# TSC8-75pld.net
KiCad netlist of a schematic drawn in EAGLE
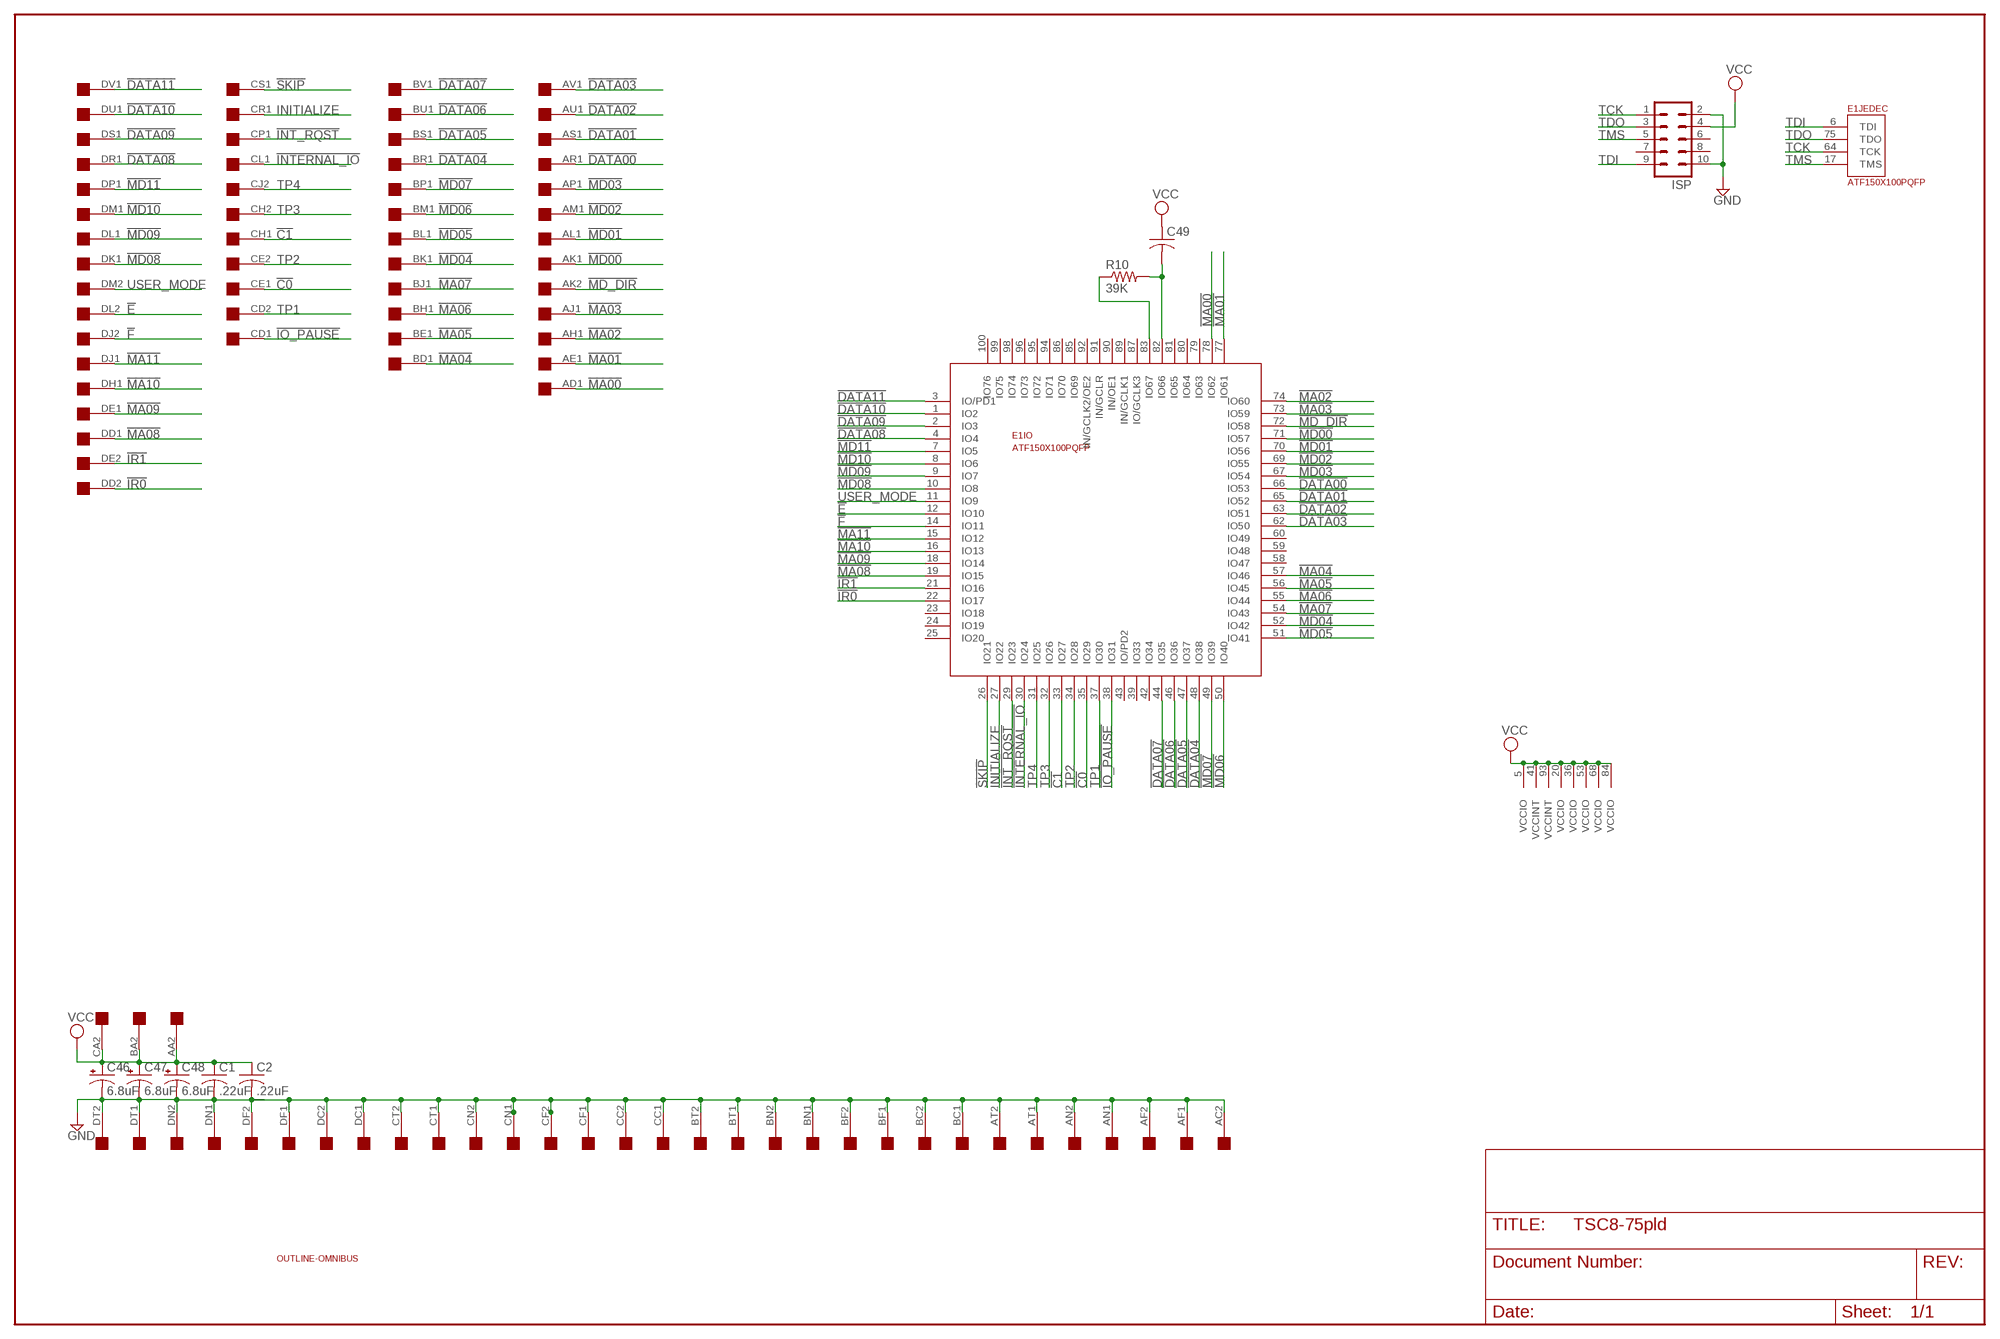
[diagram p0: schematic, sheet 1]

(export (version "E")
  (design (tool "Eeschema 10.0.6"))
  (components
    (comp (ref "C1")
      (value ".22uF")
      (footprint "eagle-import:C050-025X075")
      (libsource (lib "eagle-import") (part "C-US050-025X075"))
    )
    (comp (ref "C2")
      (value ".22uF")
      (footprint "eagle-import:C050-025X075")
      (libsource (lib "eagle-import") (part "C-US050-025X075"))
    )
    (comp (ref "C46")
      (value "6.8uF")
      (footprint "eagle-import:E12-8")
      (libsource (lib "eagle-import") (part "CPOL-USE20-8AXIAL"))
    )
    (comp (ref "C47")
      (value "6.8uF")
      (footprint "eagle-import:E12-8")
      (libsource (lib "eagle-import") (part "CPOL-USE20-8AXIAL"))
    )
    (comp (ref "C48")
      (value "6.8uF")
      (footprint "eagle-import:E12-8")
      (libsource (lib "eagle-import") (part "CPOL-USE20-8AXIAL"))
    )
    (comp (ref "C49")
      (value "C-US050-025X075")
      (footprint "eagle-import:C050-025X075")
      (libsource (lib "eagle-import") (part "C-US050-025X075"))
    )
    (comp (ref "E1")
      (value "ATF150X100PQFP")
      (footprint "eagle-import:PQFP-100")
      (libsource (lib "eagle-import") (part "ATF150X100PQFP"))
    )
    (comp (ref "EDGE")
      (value "QUAD")
      (footprint "eagle-import:EDGE-CON8")
      (libsource (lib "eagle-import") (part "QUAD"))
    )
    (comp (ref "ISP")
      (value "ML10")
      (footprint "eagle-import:ML10")
      (libsource (lib "eagle-import") (part "ML10"))
    )
    (comp (ref "R10")
      (value "39K")
      (footprint "eagle-import:0204_7")
      (libsource (lib "eagle-import") (part "R-US_0204/7"))
    )
    (comp (ref "U$1")
      (value "OUTLINE-OMNIBUS")
      (footprint "eagle-import:OMNIBUS")
      (libsource (lib "eagle-import") (part "OUTLINE-OMNIBUS"))
    )
  )
  (nets
    (net (code "1") (name "/INITIALIZE") (class "Default")
      (node (ref "E1") (pin "27") (pinfunction "IO22_27") (pintype "bidirectional"))
      (node (ref "EDGE") (pin "CR1") (pinfunction "1_CR1") (pintype "bidirectional"))
    )
    (net (code "2") (name "/TCK") (class "Default")
      (node (ref "E1") (pin "64") (pinfunction "TCK_64") (pintype "bidirectional"))
      (node (ref "ISP") (pin "1") (pinfunction "1_1") (pintype "passive"))
    )
    (net (code "3") (name "/TDI") (class "Default")
      (node (ref "E1") (pin "6") (pinfunction "TDI_6") (pintype "bidirectional"))
      (node (ref "ISP") (pin "9") (pinfunction "9_9") (pintype "passive"))
    )
    (net (code "4") (name "/TDO") (class "Default")
      (node (ref "E1") (pin "75") (pinfunction "TDO_75") (pintype "bidirectional"))
      (node (ref "ISP") (pin "3") (pinfunction "3_3") (pintype "passive"))
    )
    (net (code "5") (name "/TMS") (class "Default")
      (node (ref "E1") (pin "17") (pinfunction "TMS_17") (pintype "bidirectional"))
      (node (ref "ISP") (pin "5") (pinfunction "5_5") (pintype "passive"))
    )
    (net (code "6") (name "/TP1") (class "Default")
      (node (ref "E1") (pin "37") (pinfunction "IO30_37") (pintype "bidirectional"))
      (node (ref "EDGE") (pin "CD2") (pinfunction "1_CD2") (pintype "bidirectional"))
    )
    (net (code "7") (name "/TP2") (class "Default")
      (node (ref "E1") (pin "34") (pinfunction "IO28_34") (pintype "bidirectional"))
      (node (ref "EDGE") (pin "CE2") (pinfunction "1_CE2") (pintype "bidirectional"))
    )
    (net (code "8") (name "/TP3") (class "Default")
      (node (ref "E1") (pin "32") (pinfunction "IO26_32") (pintype "bidirectional"))
      (node (ref "EDGE") (pin "CH2") (pinfunction "1_CH2") (pintype "bidirectional"))
    )
    (net (code "9") (name "/TP4") (class "Default")
      (node (ref "E1") (pin "31") (pinfunction "IO25_31") (pintype "bidirectional"))
      (node (ref "EDGE") (pin "CJ2") (pinfunction "1_CJ2") (pintype "bidirectional"))
    )
    (net (code "10") (name "/USER_MODE") (class "Default")
      (node (ref "E1") (pin "11") (pinfunction "IO9_11") (pintype "bidirectional"))
      (node (ref "EDGE") (pin "DM2") (pinfunction "1_DM2") (pintype "bidirectional"))
    )
    (net (code "11") (name "/~{C0}") (class "Default")
      (node (ref "E1") (pin "35") (pinfunction "IO29_35") (pintype "bidirectional"))
      (node (ref "EDGE") (pin "CE1") (pinfunction "1_CE1") (pintype "bidirectional"))
    )
    (net (code "12") (name "/~{C1}") (class "Default")
      (node (ref "E1") (pin "33") (pinfunction "IO27_33") (pintype "bidirectional"))
      (node (ref "EDGE") (pin "CH1") (pinfunction "1_CH1") (pintype "bidirectional"))
    )
    (net (code "13") (name "/~{DATA00}") (class "Default")
      (node (ref "E1") (pin "66") (pinfunction "IO53_66") (pintype "bidirectional"))
      (node (ref "EDGE") (pin "AR1") (pinfunction "1_AR1") (pintype "bidirectional"))
    )
    (net (code "14") (name "/~{DATA01}") (class "Default")
      (node (ref "E1") (pin "65") (pinfunction "IO52_65") (pintype "bidirectional"))
      (node (ref "EDGE") (pin "AS1") (pinfunction "1_AS1") (pintype "bidirectional"))
    )
    (net (code "15") (name "/~{DATA02}") (class "Default")
      (node (ref "E1") (pin "63") (pinfunction "IO51_63") (pintype "bidirectional"))
      (node (ref "EDGE") (pin "AU1") (pinfunction "1_AU1") (pintype "bidirectional"))
    )
    (net (code "16") (name "/~{DATA03}") (class "Default")
      (node (ref "E1") (pin "62") (pinfunction "IO50_62") (pintype "bidirectional"))
      (node (ref "EDGE") (pin "AV1") (pinfunction "1_AV1") (pintype "bidirectional"))
    )
    (net (code "17") (name "/~{DATA04}") (class "Default")
      (node (ref "E1") (pin "48") (pinfunction "IO38_48") (pintype "bidirectional"))
      (node (ref "EDGE") (pin "BR1") (pinfunction "1_BR1") (pintype "bidirectional"))
    )
    (net (code "18") (name "/~{DATA05}") (class "Default")
      (node (ref "E1") (pin "47") (pinfunction "IO37_47") (pintype "bidirectional"))
      (node (ref "EDGE") (pin "BS1") (pinfunction "1_BS1") (pintype "bidirectional"))
    )
    (net (code "19") (name "/~{DATA06}") (class "Default")
      (node (ref "E1") (pin "46") (pinfunction "IO36_46") (pintype "bidirectional"))
      (node (ref "EDGE") (pin "BU1") (pinfunction "1_BU1") (pintype "bidirectional"))
    )
    (net (code "20") (name "/~{DATA07}") (class "Default")
      (node (ref "E1") (pin "44") (pinfunction "IO35_44") (pintype "bidirectional"))
      (node (ref "EDGE") (pin "BV1") (pinfunction "1_BV1") (pintype "bidirectional"))
    )
    (net (code "21") (name "/~{DATA08}") (class "Default")
      (node (ref "E1") (pin "4") (pinfunction "IO4_4") (pintype "bidirectional"))
      (node (ref "EDGE") (pin "DR1") (pinfunction "1_DR1") (pintype "bidirectional"))
    )
    (net (code "22") (name "/~{DATA09}") (class "Default")
      (node (ref "E1") (pin "2") (pinfunction "IO3_2") (pintype "bidirectional"))
      (node (ref "EDGE") (pin "DS1") (pinfunction "1_DS1") (pintype "bidirectional"))
    )
    (net (code "23") (name "/~{DATA10}") (class "Default")
      (node (ref "E1") (pin "1") (pinfunction "IO2_1") (pintype "bidirectional"))
      (node (ref "EDGE") (pin "DU1") (pinfunction "1_DU1") (pintype "bidirectional"))
    )
    (net (code "24") (name "/~{DATA11}") (class "Default")
      (node (ref "E1") (pin "3") (pinfunction "IO/PD1_3") (pintype "bidirectional"))
      (node (ref "EDGE") (pin "DV1") (pinfunction "1_DV1") (pintype "bidirectional"))
    )
    (net (code "25") (name "/~{E}") (class "Default")
      (node (ref "E1") (pin "12") (pinfunction "IO10_12") (pintype "bidirectional"))
      (node (ref "EDGE") (pin "DL2") (pinfunction "1_DL2") (pintype "bidirectional"))
    )
    (net (code "26") (name "/~{F}") (class "Default")
      (node (ref "E1") (pin "14") (pinfunction "IO11_14") (pintype "bidirectional"))
      (node (ref "EDGE") (pin "DJ2") (pinfunction "1_DJ2") (pintype "bidirectional"))
    )
    (net (code "27") (name "/~{INTERNAL_IO}") (class "Default")
      (node (ref "E1") (pin "30") (pinfunction "IO24_30") (pintype "bidirectional"))
      (node (ref "EDGE") (pin "CL1") (pinfunction "1_CL1") (pintype "bidirectional"))
    )
    (net (code "28") (name "/~{INT_RQST}") (class "Default")
      (node (ref "E1") (pin "29") (pinfunction "IO23_29") (pintype "bidirectional"))
      (node (ref "EDGE") (pin "CP1") (pinfunction "1_CP1") (pintype "bidirectional"))
    )
    (net (code "29") (name "/~{IO_PAUSE}") (class "Default")
      (node (ref "E1") (pin "38") (pinfunction "IO31_38") (pintype "bidirectional"))
      (node (ref "EDGE") (pin "CD1") (pinfunction "1_CD1") (pintype "bidirectional"))
    )
    (net (code "30") (name "/~{IR0}") (class "Default")
      (node (ref "E1") (pin "22") (pinfunction "IO17_22") (pintype "bidirectional"))
      (node (ref "EDGE") (pin "DD2") (pinfunction "1_DD2") (pintype "bidirectional"))
    )
    (net (code "31") (name "/~{IR1}") (class "Default")
      (node (ref "E1") (pin "21") (pinfunction "IO16_21") (pintype "bidirectional"))
      (node (ref "EDGE") (pin "DE2") (pinfunction "1_DE2") (pintype "bidirectional"))
    )
    (net (code "32") (name "/~{MA00}") (class "Default")
      (node (ref "E1") (pin "78") (pinfunction "IO62_78") (pintype "bidirectional"))
      (node (ref "EDGE") (pin "AD1") (pinfunction "1_AD1") (pintype "bidirectional"))
    )
    (net (code "33") (name "/~{MA01}") (class "Default")
      (node (ref "E1") (pin "77") (pinfunction "IO61_77") (pintype "bidirectional"))
      (node (ref "EDGE") (pin "AE1") (pinfunction "1_AE1") (pintype "bidirectional"))
    )
    (net (code "34") (name "/~{MA02}") (class "Default")
      (node (ref "E1") (pin "74") (pinfunction "IO60_74") (pintype "bidirectional"))
      (node (ref "EDGE") (pin "AH1") (pinfunction "1_AH1") (pintype "bidirectional"))
    )
    (net (code "35") (name "/~{MA03}") (class "Default")
      (node (ref "E1") (pin "73") (pinfunction "IO59_73") (pintype "bidirectional"))
      (node (ref "EDGE") (pin "AJ1") (pinfunction "1_AJ1") (pintype "bidirectional"))
    )
    (net (code "36") (name "/~{MA04}") (class "Default")
      (node (ref "E1") (pin "57") (pinfunction "IO46_57") (pintype "bidirectional"))
      (node (ref "EDGE") (pin "BD1") (pinfunction "1_BD1") (pintype "bidirectional"))
    )
    (net (code "37") (name "/~{MA05}") (class "Default")
      (node (ref "E1") (pin "56") (pinfunction "IO45_56") (pintype "bidirectional"))
      (node (ref "EDGE") (pin "BE1") (pinfunction "1_BE1") (pintype "bidirectional"))
    )
    (net (code "38") (name "/~{MA06}") (class "Default")
      (node (ref "E1") (pin "55") (pinfunction "IO44_55") (pintype "bidirectional"))
      (node (ref "EDGE") (pin "BH1") (pinfunction "1_BH1") (pintype "bidirectional"))
    )
    (net (code "39") (name "/~{MA07}") (class "Default")
      (node (ref "E1") (pin "54") (pinfunction "IO43_54") (pintype "bidirectional"))
      (node (ref "EDGE") (pin "BJ1") (pinfunction "1_BJ1") (pintype "bidirectional"))
    )
    (net (code "40") (name "/~{MA08}") (class "Default")
      (node (ref "E1") (pin "19") (pinfunction "IO15_19") (pintype "bidirectional"))
      (node (ref "EDGE") (pin "DD1") (pinfunction "1_DD1") (pintype "bidirectional"))
    )
    (net (code "41") (name "/~{MA09}") (class "Default")
      (node (ref "E1") (pin "18") (pinfunction "IO14_18") (pintype "bidirectional"))
      (node (ref "EDGE") (pin "DE1") (pinfunction "1_DE1") (pintype "bidirectional"))
    )
    (net (code "42") (name "/~{MA10}") (class "Default")
      (node (ref "E1") (pin "16") (pinfunction "IO13_16") (pintype "bidirectional"))
      (node (ref "EDGE") (pin "DH1") (pinfunction "1_DH1") (pintype "bidirectional"))
    )
    (net (code "43") (name "/~{MA11}") (class "Default")
      (node (ref "E1") (pin "15") (pinfunction "IO12_15") (pintype "bidirectional"))
      (node (ref "EDGE") (pin "DJ1") (pinfunction "1_DJ1") (pintype "bidirectional"))
    )
    (net (code "44") (name "/~{MD00}") (class "Default")
      (node (ref "E1") (pin "71") (pinfunction "IO57_71") (pintype "bidirectional"))
      (node (ref "EDGE") (pin "AK1") (pinfunction "1_AK1") (pintype "bidirectional"))
    )
    (net (code "45") (name "/~{MD01}") (class "Default")
      (node (ref "E1") (pin "70") (pinfunction "IO56_70") (pintype "bidirectional"))
      (node (ref "EDGE") (pin "AL1") (pinfunction "1_AL1") (pintype "bidirectional"))
    )
    (net (code "46") (name "/~{MD02}") (class "Default")
      (node (ref "E1") (pin "69") (pinfunction "IO55_69") (pintype "bidirectional"))
      (node (ref "EDGE") (pin "AM1") (pinfunction "1_AM1") (pintype "bidirectional"))
    )
    (net (code "47") (name "/~{MD03}") (class "Default")
      (node (ref "E1") (pin "67") (pinfunction "IO54_67") (pintype "bidirectional"))
      (node (ref "EDGE") (pin "AP1") (pinfunction "1_AP1") (pintype "bidirectional"))
    )
    (net (code "48") (name "/~{MD04}") (class "Default")
      (node (ref "E1") (pin "52") (pinfunction "IO42_52") (pintype "bidirectional"))
      (node (ref "EDGE") (pin "BK1") (pinfunction "1_BK1") (pintype "bidirectional"))
    )
    (net (code "49") (name "/~{MD05}") (class "Default")
      (node (ref "E1") (pin "51") (pinfunction "IO41_51") (pintype "bidirectional"))
      (node (ref "EDGE") (pin "BL1") (pinfunction "1_BL1") (pintype "bidirectional"))
    )
    (net (code "50") (name "/~{MD06}") (class "Default")
      (node (ref "E1") (pin "50") (pinfunction "IO40_50") (pintype "bidirectional"))
      (node (ref "EDGE") (pin "BM1") (pinfunction "1_BM1") (pintype "bidirectional"))
    )
    (net (code "51") (name "/~{MD07}") (class "Default")
      (node (ref "E1") (pin "49") (pinfunction "IO39_49") (pintype "bidirectional"))
      (node (ref "EDGE") (pin "BP1") (pinfunction "1_BP1") (pintype "bidirectional"))
    )
    (net (code "52") (name "/~{MD08}") (class "Default")
      (node (ref "E1") (pin "10") (pinfunction "IO8_10") (pintype "bidirectional"))
      (node (ref "EDGE") (pin "DK1") (pinfunction "1_DK1") (pintype "bidirectional"))
    )
    (net (code "53") (name "/~{MD09}") (class "Default")
      (node (ref "E1") (pin "9") (pinfunction "IO7_9") (pintype "bidirectional"))
      (node (ref "EDGE") (pin "DL1") (pinfunction "1_DL1") (pintype "bidirectional"))
    )
    (net (code "54") (name "/~{MD10}") (class "Default")
      (node (ref "E1") (pin "8") (pinfunction "IO6_8") (pintype "bidirectional"))
      (node (ref "EDGE") (pin "DM1") (pinfunction "1_DM1") (pintype "bidirectional"))
    )
    (net (code "55") (name "/~{MD11}") (class "Default")
      (node (ref "E1") (pin "7") (pinfunction "IO5_7") (pintype "bidirectional"))
      (node (ref "EDGE") (pin "DP1") (pinfunction "1_DP1") (pintype "bidirectional"))
    )
    (net (code "56") (name "/~{MD_DIR}") (class "Default")
      (node (ref "E1") (pin "72") (pinfunction "IO58_72") (pintype "bidirectional"))
      (node (ref "EDGE") (pin "AK2") (pinfunction "1_AK2") (pintype "bidirectional"))
    )
    (net (code "57") (name "/~{SKIP}") (class "Default")
      (node (ref "E1") (pin "26") (pinfunction "IO21_26") (pintype "bidirectional"))
      (node (ref "EDGE") (pin "CS1") (pinfunction "1_CS1") (pintype "bidirectional"))
    )
    (net (code "58") (name "GND") (class "Default")
      (node (ref "C1") (pin "2") (pinfunction "2_2") (pintype "passive"))
      (node (ref "C2") (pin "2") (pinfunction "2_2") (pintype "passive"))
      (node (ref "C46") (pin "-") (pinfunction "-_-") (pintype "passive"))
      (node (ref "C47") (pin "-") (pinfunction "-_-") (pintype "passive"))
      (node (ref "C48") (pin "-") (pinfunction "-_-") (pintype "passive"))
      (node (ref "EDGE") (pin "AC2") (pinfunction "1_AC2") (pintype "bidirectional"))
      (node (ref "EDGE") (pin "AF1") (pinfunction "1_AF1") (pintype "bidirectional"))
      (node (ref "EDGE") (pin "AF2") (pinfunction "1_AF2") (pintype "bidirectional"))
      (node (ref "EDGE") (pin "AN1") (pinfunction "1_AN1") (pintype "bidirectional"))
      (node (ref "EDGE") (pin "AN2") (pinfunction "1_AN2") (pintype "bidirectional"))
      (node (ref "EDGE") (pin "AT1") (pinfunction "1_AT1") (pintype "bidirectional"))
      (node (ref "EDGE") (pin "AT2") (pinfunction "1_AT2") (pintype "bidirectional"))
      (node (ref "EDGE") (pin "BC1") (pinfunction "1_BC1") (pintype "bidirectional"))
      (node (ref "EDGE") (pin "BC2") (pinfunction "1_BC2") (pintype "bidirectional"))
      (node (ref "EDGE") (pin "BF1") (pinfunction "1_BF1") (pintype "bidirectional"))
      (node (ref "EDGE") (pin "BF2") (pinfunction "1_BF2") (pintype "bidirectional"))
      (node (ref "EDGE") (pin "BN1") (pinfunction "1_BN1") (pintype "bidirectional"))
      (node (ref "EDGE") (pin "BN2") (pinfunction "1_BN2") (pintype "bidirectional"))
      (node (ref "EDGE") (pin "BT1") (pinfunction "1_BT1") (pintype "bidirectional"))
      (node (ref "EDGE") (pin "BT2") (pinfunction "1_BT2") (pintype "bidirectional"))
      (node (ref "EDGE") (pin "CC1") (pinfunction "1_CC1") (pintype "bidirectional"))
      (node (ref "EDGE") (pin "CC2") (pinfunction "1_CC2") (pintype "bidirectional"))
      (node (ref "EDGE") (pin "CF1") (pinfunction "1_CF1") (pintype "bidirectional"))
      (node (ref "EDGE") (pin "CF2") (pinfunction "1_CF2") (pintype "bidirectional"))
      (node (ref "EDGE") (pin "CN1") (pinfunction "1_CN1") (pintype "bidirectional"))
      (node (ref "EDGE") (pin "CN2") (pinfunction "1_CN2") (pintype "bidirectional"))
      (node (ref "EDGE") (pin "CT1") (pinfunction "1_CT1") (pintype "bidirectional"))
      (node (ref "EDGE") (pin "CT2") (pinfunction "1_CT2") (pintype "bidirectional"))
      (node (ref "EDGE") (pin "DC1") (pinfunction "1_DC1") (pintype "bidirectional"))
      (node (ref "EDGE") (pin "DC2") (pinfunction "1_DC2") (pintype "bidirectional"))
      (node (ref "EDGE") (pin "DF1") (pinfunction "1_DF1") (pintype "bidirectional"))
      (node (ref "EDGE") (pin "DF2") (pinfunction "1_DF2") (pintype "bidirectional"))
      (node (ref "EDGE") (pin "DN1") (pinfunction "1_DN1") (pintype "bidirectional"))
      (node (ref "EDGE") (pin "DN2") (pinfunction "1_DN2") (pintype "bidirectional"))
      (node (ref "EDGE") (pin "DT1") (pinfunction "1_DT1") (pintype "bidirectional"))
      (node (ref "EDGE") (pin "DT2") (pinfunction "1_DT2") (pintype "bidirectional"))
      (node (ref "ISP") (pin "10") (pinfunction "10_10") (pintype "passive"))
      (node (ref "ISP") (pin "2") (pinfunction "2_2") (pintype "passive"))
    )
    (net (code "59") (name "Net-(E1Q-IO66)") (class "Default")
      (node (ref "C49") (pin "2") (pinfunction "2_2") (pintype "passive"))
      (node (ref "E1") (pin "82") (pinfunction "IO66_82") (pintype "bidirectional"))
      (node (ref "R10") (pin "2") (pinfunction "2_2") (pintype "passive"))
    )
    (net (code "60") (name "Net-(E1Q-IO67)") (class "Default")
      (node (ref "E1") (pin "83") (pinfunction "IO67_83") (pintype "bidirectional"))
      (node (ref "R10") (pin "1") (pinfunction "1_1") (pintype "passive"))
    )
    (net (code "61") (name "VCC") (class "Default")
      (node (ref "C1") (pin "1") (pinfunction "1_1") (pintype "passive"))
      (node (ref "C2") (pin "1") (pinfunction "1_1") (pintype "passive"))
      (node (ref "C46") (pin "+") (pinfunction "+_+") (pintype "passive"))
      (node (ref "C47") (pin "+") (pinfunction "+_+") (pintype "passive"))
      (node (ref "C48") (pin "+") (pinfunction "+_+") (pintype "passive"))
      (node (ref "C49") (pin "1") (pinfunction "1_1") (pintype "passive"))
      (node (ref "E1") (pin "20") (pinfunction "VCCIO_20") (pintype "power_in"))
      (node (ref "E1") (pin "36") (pinfunction "VCCIO_36") (pintype "power_in"))
      (node (ref "E1") (pin "41") (pinfunction "VCCINT_41") (pintype "power_in"))
      (node (ref "E1") (pin "5") (pinfunction "VCCIO_5") (pintype "power_in"))
      (node (ref "E1") (pin "53") (pinfunction "VCCIO_53") (pintype "power_in"))
      (node (ref "E1") (pin "68") (pinfunction "VCCIO_68") (pintype "power_in"))
      (node (ref "E1") (pin "84") (pinfunction "VCCIO_84") (pintype "power_in"))
      (node (ref "E1") (pin "93") (pinfunction "VCCINT_93") (pintype "power_in"))
      (node (ref "EDGE") (pin "AA2") (pinfunction "1_AA2") (pintype "bidirectional"))
      (node (ref "EDGE") (pin "BA2") (pinfunction "1_BA2") (pintype "bidirectional"))
      (node (ref "EDGE") (pin "CA2") (pinfunction "1_CA2") (pintype "bidirectional"))
      (node (ref "ISP") (pin "4") (pinfunction "4_4") (pintype "passive"))
    )
    (net (code "62") (name "unconnected-(E1Q-IN{slash}GCLK1-Pad89)") (class "Default")
      (node (ref "E1") (pin "89") (pinfunction "IN/GCLK1_89") (pintype "input"))
    )
    (net (code "63") (name "unconnected-(E1Q-IN{slash}GCLK2{slash}OE2-Pad92)") (class "Default")
      (node (ref "E1") (pin "92") (pinfunction "IN/GCLK2/OE2_92") (pintype "input"))
    )
    (net (code "64") (name "unconnected-(E1Q-IN{slash}GCLR-Pad91)") (class "Default")
      (node (ref "E1") (pin "91") (pinfunction "IN/GCLR_91") (pintype "input"))
    )
    (net (code "65") (name "unconnected-(E1Q-IN{slash}OE1-Pad90)") (class "Default")
      (node (ref "E1") (pin "90") (pinfunction "IN/OE1_90") (pintype "input"))
    )
    (net (code "66") (name "unconnected-(E1Q-IO18-Pad23)") (class "Default")
      (node (ref "E1") (pin "23") (pinfunction "IO18_23") (pintype "bidirectional"))
    )
    (net (code "67") (name "unconnected-(E1Q-IO19-Pad24)") (class "Default")
      (node (ref "E1") (pin "24") (pinfunction "IO19_24") (pintype "bidirectional"))
    )
    (net (code "68") (name "unconnected-(E1Q-IO20-Pad25)") (class "Default")
      (node (ref "E1") (pin "25") (pinfunction "IO20_25") (pintype "bidirectional"))
    )
    (net (code "69") (name "unconnected-(E1Q-IO33-Pad39)") (class "Default")
      (node (ref "E1") (pin "39") (pinfunction "IO33_39") (pintype "bidirectional"))
    )
    (net (code "70") (name "unconnected-(E1Q-IO34-Pad42)") (class "Default")
      (node (ref "E1") (pin "42") (pinfunction "IO34_42") (pintype "bidirectional"))
    )
    (net (code "71") (name "unconnected-(E1Q-IO47-Pad58)") (class "Default")
      (node (ref "E1") (pin "58") (pinfunction "IO47_58") (pintype "bidirectional"))
    )
    (net (code "72") (name "unconnected-(E1Q-IO48-Pad59)") (class "Default")
      (node (ref "E1") (pin "59") (pinfunction "IO48_59") (pintype "bidirectional"))
    )
    (net (code "73") (name "unconnected-(E1Q-IO49-Pad60)") (class "Default")
      (node (ref "E1") (pin "60") (pinfunction "IO49_60") (pintype "bidirectional"))
    )
    (net (code "74") (name "unconnected-(E1Q-IO63-Pad79)") (class "Default")
      (node (ref "E1") (pin "79") (pinfunction "IO63_79") (pintype "bidirectional"))
    )
    (net (code "75") (name "unconnected-(E1Q-IO64-Pad80)") (class "Default")
      (node (ref "E1") (pin "80") (pinfunction "IO64_80") (pintype "bidirectional"))
    )
    (net (code "76") (name "unconnected-(E1Q-IO65-Pad81)") (class "Default")
      (node (ref "E1") (pin "81") (pinfunction "IO65_81") (pintype "bidirectional"))
    )
    (net (code "77") (name "unconnected-(E1Q-IO69-Pad85)") (class "Default")
      (node (ref "E1") (pin "85") (pinfunction "IO69_85") (pintype "bidirectional"))
    )
    (net (code "78") (name "unconnected-(E1Q-IO70-Pad86)") (class "Default")
      (node (ref "E1") (pin "86") (pinfunction "IO70_86") (pintype "bidirectional"))
    )
    (net (code "79") (name "unconnected-(E1Q-IO71-Pad94)") (class "Default")
      (node (ref "E1") (pin "94") (pinfunction "IO71_94") (pintype "bidirectional"))
    )
    (net (code "80") (name "unconnected-(E1Q-IO72-Pad95)") (class "Default")
      (node (ref "E1") (pin "95") (pinfunction "IO72_95") (pintype "bidirectional"))
    )
    (net (code "81") (name "unconnected-(E1Q-IO73-Pad96)") (class "Default")
      (node (ref "E1") (pin "96") (pinfunction "IO73_96") (pintype "bidirectional"))
    )
    (net (code "82") (name "unconnected-(E1Q-IO74-Pad98)") (class "Default")
      (node (ref "E1") (pin "98") (pinfunction "IO74_98") (pintype "bidirectional"))
    )
    (net (code "83") (name "unconnected-(E1Q-IO75-Pad99)") (class "Default")
      (node (ref "E1") (pin "99") (pinfunction "IO75_99") (pintype "bidirectional"))
    )
    (net (code "84") (name "unconnected-(E1Q-IO76-Pad100)") (class "Default")
      (node (ref "E1") (pin "100") (pinfunction "IO76_100") (pintype "bidirectional"))
    )
    (net (code "85") (name "unconnected-(E1Q-IO{slash}GCLK3-Pad87)") (class "Default")
      (node (ref "E1") (pin "87") (pinfunction "IO/GCLK3_87") (pintype "bidirectional"))
    )
    (net (code "86") (name "unconnected-(E1Q-IO{slash}PD2-Pad43)") (class "Default")
      (node (ref "E1") (pin "43") (pinfunction "IO/PD2_43") (pintype "bidirectional"))
    )
    (net (code "87") (name "unconnected-(ISP-Pad6)") (class "Default")
      (node (ref "ISP") (pin "6") (pinfunction "6_6") (pintype "passive"))
    )
    (net (code "88") (name "unconnected-(ISP-Pad7)") (class "Default")
      (node (ref "ISP") (pin "7") (pinfunction "7_7") (pintype "passive"))
    )
    (net (code "89") (name "unconnected-(ISP-Pad8)") (class "Default")
      (node (ref "ISP") (pin "8") (pinfunction "8_8") (pintype "passive"))
    )
  )
)
